# FMC_Memory.net
KiCad netlist of a schematic drawn in Altium Designer
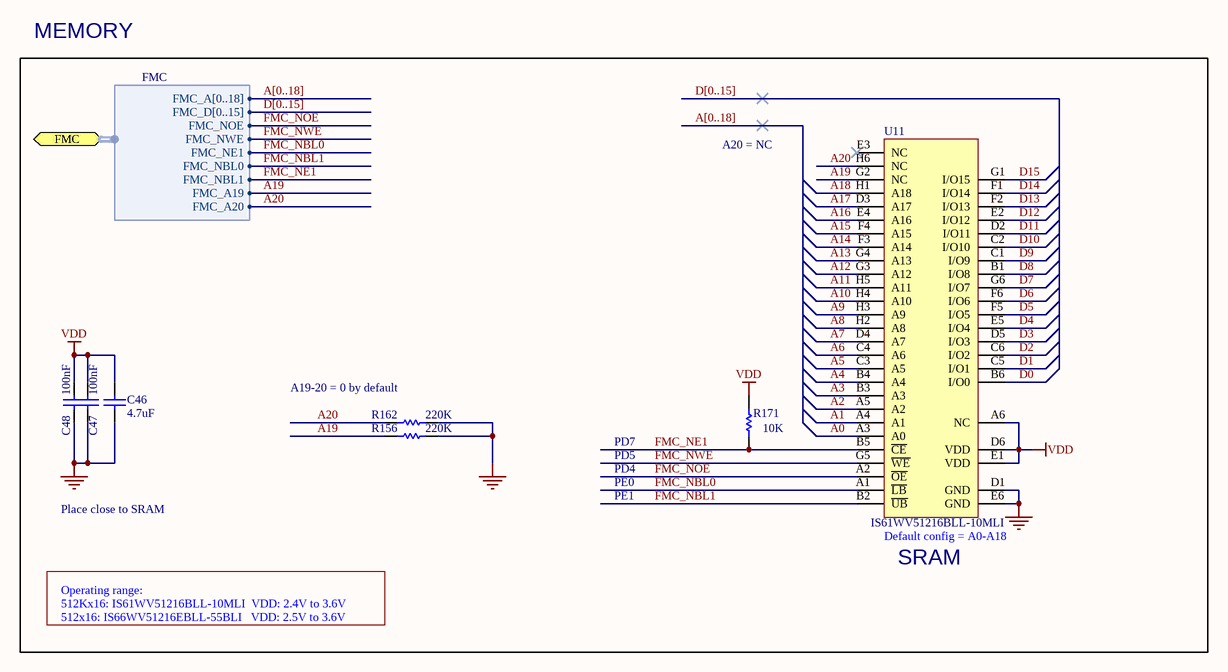
[diagram p0: FMC Memory.SchDoc]

(export (version "E")
  (design (tool "Eeschema 10.0.6"))
  (components
    (comp (ref "C46")
      (value "4.7uF")
      (footprint "C0603")
      (description "Capacitor, MLCC, 4.7uF, 16V, X5R, 10%, 0603, T=0.8mm")
      (fields
        (field (name "INTERNAL_PART_NUMBER") "MCD-00009")
        (field (name "MANUFACTURER_PART_NUMBER") "CC0603KRX5R7BB475")
        (field (name "PROVIDED_BY") "SUBCO")
      )
      (libsource (lib "MCD_PARTS_database") (part "Capacitor"))
    )
    (comp (ref "C47")
      (value "100nF")
      (footprint "C0402")
      (description "Capacitor, MLCC, 100nF, 16V, X7R, 10%, 0402, T=0.5mm")
      (fields
        (field (name "INTERNAL_PART_NUMBER") "MCD-00006")
        (field (name "MANUFACTURER_PART_NUMBER") "CC0402KRX7R7BB104")
        (field (name "PROVIDED_BY") "SUBCO")
      )
      (libsource (lib "MCD_PARTS_database") (part "Capacitor"))
    )
    (comp (ref "C48")
      (value "100nF")
      (footprint "C0402")
      (description "Capacitor, MLCC, 100nF, 16V, X7R, 10%, 0402, T=0.5mm")
      (fields
        (field (name "INTERNAL_PART_NUMBER") "MCD-00006")
        (field (name "MANUFACTURER_PART_NUMBER") "CC0402KRX7R7BB104")
        (field (name "PROVIDED_BY") "SUBCO")
      )
      (libsource (lib "MCD_PARTS_database") (part "Capacitor"))
    )
    (comp (ref "R156")
      (value "220K")
      (footprint "R0402")
      (description "Resistor,220K,0402,1%,1/16W")
      (fields
        (field (name "INTERNAL_PART_NUMBER") "MCD-00164")
        (field (name "MANUFACTURER_PART_NUMBER") "RC0402FR-07220KL")
        (field (name "PROVIDED_BY") "SUBCO")
      )
      (libsource (lib "MCD_PARTS_database") (part "Resistor"))
    )
    (comp (ref "R162")
      (value "220K")
      (footprint "R0402")
      (description "Resistor,220K,0402,1%,1/16W")
      (fields
        (field (name "INTERNAL_PART_NUMBER") "MCD-00164")
        (field (name "MANUFACTURER_PART_NUMBER") "RC0402FR-07220KL")
        (field (name "PROVIDED_BY") "SUBCO")
      )
      (libsource (lib "MCD_PARTS_database") (part "Resistor"))
    )
    (comp (ref "R171")
      (value "10K")
      (footprint "R0402")
      (description "Resistor,10K,0402,1%,1/16W")
      (fields
        (field (name "INTERNAL_PART_NUMBER") "MCD-00053")
        (field (name "MANUFACTURER_PART_NUMBER") "RC0402FR-0710KL")
        (field (name "PROVIDED_BY") "SUBCO")
      )
      (libsource (lib "MCD_PARTS_database") (part "Resistor"))
    )
    (comp (ref "U11")
      (value "IS61WV51216BLL-10MLI")
      (footprint "ICC_MINI-BGA48_9X11_P075")
      (description "SRAM, 8Mb, 10ns, 512Kx16bits, Async, 3.3v")
      (fields
        (field (name "INTERNAL_PART_NUMBER") "MCD-01071")
        (field (name "MANUFACTURER") "ISSI")
        (field (name "PROVIDED_BY") "SUBCO")
      )
      (libsource (lib "MCD_PARTS_database") (part "IS61WV51216BLL-10MLI"))
    )
  )
  (nets
    (net (code "2") (name "/A0") (class "Default")
      (node (ref "U11") (pin "A3") (pinfunction "A0_A3") (pintype "passive"))
    )
    (net (code "3") (name "/A1") (class "Default")
      (node (ref "U11") (pin "A4") (pinfunction "A1_A4") (pintype "passive"))
    )
    (net (code "4") (name "/A2") (class "Default")
      (node (ref "U11") (pin "A5") (pinfunction "A2_A5") (pintype "passive"))
    )
    (net (code "5") (name "/A3") (class "Default")
      (node (ref "U11") (pin "B3") (pinfunction "A3_B3") (pintype "passive"))
    )
    (net (code "6") (name "/A4") (class "Default")
      (node (ref "U11") (pin "B4") (pinfunction "A4_B4") (pintype "passive"))
    )
    (net (code "7") (name "/A5") (class "Default")
      (node (ref "U11") (pin "C3") (pinfunction "A5_C3") (pintype "passive"))
    )
    (net (code "8") (name "/A6") (class "Default")
      (node (ref "U11") (pin "C4") (pinfunction "A6_C4") (pintype "passive"))
    )
    (net (code "9") (name "/A7") (class "Default")
      (node (ref "U11") (pin "D4") (pinfunction "A7_D4") (pintype "passive"))
    )
    (net (code "10") (name "/A8") (class "Default")
      (node (ref "U11") (pin "H2") (pinfunction "A8_H2") (pintype "passive"))
    )
    (net (code "11") (name "/A9") (class "Default")
      (node (ref "U11") (pin "H3") (pinfunction "A9_H3") (pintype "passive"))
    )
    (net (code "12") (name "/A10") (class "Default")
      (node (ref "U11") (pin "H4") (pinfunction "A10_H4") (pintype "passive"))
    )
    (net (code "13") (name "/A11") (class "Default")
      (node (ref "U11") (pin "H5") (pinfunction "A11_H5") (pintype "passive"))
    )
    (net (code "14") (name "/A12") (class "Default")
      (node (ref "U11") (pin "G3") (pinfunction "A12_G3") (pintype "passive"))
    )
    (net (code "15") (name "/A13") (class "Default")
      (node (ref "U11") (pin "G4") (pinfunction "A13_G4") (pintype "passive"))
    )
    (net (code "16") (name "/A14") (class "Default")
      (node (ref "U11") (pin "F3") (pinfunction "A14_F3") (pintype "passive"))
    )
    (net (code "17") (name "/A15") (class "Default")
      (node (ref "U11") (pin "F4") (pinfunction "A15_F4") (pintype "passive"))
    )
    (net (code "18") (name "/A16") (class "Default")
      (node (ref "U11") (pin "E4") (pinfunction "A16_E4") (pintype "passive"))
    )
    (net (code "19") (name "/A17") (class "Default")
      (node (ref "U11") (pin "D3") (pinfunction "A17_D3") (pintype "passive"))
    )
    (net (code "20") (name "/A18") (class "Default")
      (node (ref "U11") (pin "H1") (pinfunction "A18_H1") (pintype "passive"))
    )
    (net (code "21") (name "/A19") (class "Default")
      (node (ref "R156") (pin "2") (pinfunction "2_2") (pintype "passive"))
      (node (ref "U11") (pin "G2") (pinfunction "NC_G2") (pintype "passive"))
    )
    (net (code "22") (name "/A20") (class "Default")
      (node (ref "R162") (pin "2") (pinfunction "2_2") (pintype "passive"))
      (node (ref "U11") (pin "H6") (pinfunction "NC_H6") (pintype "passive"))
    )
    (net (code "24") (name "/D0") (class "Default")
      (node (ref "U11") (pin "B6") (pinfunction "I/O0_B6") (pintype "passive"))
    )
    (net (code "25") (name "/D1") (class "Default")
      (node (ref "U11") (pin "C5") (pinfunction "I/O1_C5") (pintype "passive"))
    )
    (net (code "26") (name "/D2") (class "Default")
      (node (ref "U11") (pin "C6") (pinfunction "I/O2_C6") (pintype "passive"))
    )
    (net (code "27") (name "/D3") (class "Default")
      (node (ref "U11") (pin "D5") (pinfunction "I/O3_D5") (pintype "passive"))
    )
    (net (code "28") (name "/D4") (class "Default")
      (node (ref "U11") (pin "E5") (pinfunction "I/O4_E5") (pintype "passive"))
    )
    (net (code "29") (name "/D5") (class "Default")
      (node (ref "U11") (pin "F5") (pinfunction "I/O5_F5") (pintype "passive"))
    )
    (net (code "30") (name "/D6") (class "Default")
      (node (ref "U11") (pin "F6") (pinfunction "I/O6_F6") (pintype "passive"))
    )
    (net (code "31") (name "/D7") (class "Default")
      (node (ref "U11") (pin "G6") (pinfunction "I/O7_G6") (pintype "passive"))
    )
    (net (code "32") (name "/D8") (class "Default")
      (node (ref "U11") (pin "B1") (pinfunction "I/O8_B1") (pintype "passive"))
    )
    (net (code "33") (name "/D9") (class "Default")
      (node (ref "U11") (pin "C1") (pinfunction "I/O9_C1") (pintype "passive"))
    )
    (net (code "34") (name "/D10") (class "Default")
      (node (ref "U11") (pin "C2") (pinfunction "I/O10_C2") (pintype "passive"))
    )
    (net (code "35") (name "/D11") (class "Default")
      (node (ref "U11") (pin "D2") (pinfunction "I/O11_D2") (pintype "passive"))
    )
    (net (code "36") (name "/D12") (class "Default")
      (node (ref "U11") (pin "E2") (pinfunction "I/O12_E2") (pintype "passive"))
    )
    (net (code "37") (name "/D13") (class "Default")
      (node (ref "U11") (pin "F2") (pinfunction "I/O13_F2") (pintype "passive"))
    )
    (net (code "38") (name "/D14") (class "Default")
      (node (ref "U11") (pin "F1") (pinfunction "I/O14_F1") (pintype "passive"))
    )
    (net (code "39") (name "/D15") (class "Default")
      (node (ref "U11") (pin "G1") (pinfunction "I/O15_G1") (pintype "passive"))
    )
    (net (code "41") (name "/FMC_NBL0") (class "Default")
      (node (ref "U11") (pin "A1") (pinfunction "~{LB}_A1") (pintype "passive"))
    )
    (net (code "42") (name "/FMC_NBL1") (class "Default")
      (node (ref "U11") (pin "B2") (pinfunction "~{UB}_B2") (pintype "passive"))
    )
    (net (code "43") (name "/FMC_NE1") (class "Default")
      (node (ref "R171") (pin "1") (pinfunction "1_1") (pintype "passive"))
      (node (ref "U11") (pin "B5") (pinfunction "~{CE}_B5") (pintype "passive"))
    )
    (net (code "44") (name "/FMC_NOE") (class "Default")
      (node (ref "U11") (pin "A2") (pinfunction "~{OE}_A2") (pintype "passive"))
    )
    (net (code "45") (name "/FMC_NWE") (class "Default")
      (node (ref "U11") (pin "G5") (pinfunction "~{WE}_G5") (pintype "passive"))
    )
    (net (code "48") (name "GND") (class "Default")
      (node (ref "C46") (pin "1") (pinfunction "1_1") (pintype "passive"))
      (node (ref "C47") (pin "2") (pinfunction "2_2") (pintype "passive"))
      (node (ref "C48") (pin "2") (pinfunction "2_2") (pintype "passive"))
      (node (ref "R156") (pin "1") (pinfunction "1_1") (pintype "passive"))
      (node (ref "R162") (pin "1") (pinfunction "1_1") (pintype "passive"))
      (node (ref "U11") (pin "D1") (pinfunction "GND_D1") (pintype "passive"))
      (node (ref "U11") (pin "E6") (pinfunction "GND_E6") (pintype "passive"))
    )
    (net (code "49") (name "VDD") (class "Default")
      (node (ref "C46") (pin "2") (pinfunction "2_2") (pintype "passive"))
      (node (ref "C47") (pin "1") (pinfunction "1_1") (pintype "passive"))
      (node (ref "C48") (pin "1") (pinfunction "1_1") (pintype "passive"))
      (node (ref "R171") (pin "2") (pinfunction "2_2") (pintype "passive"))
      (node (ref "U11") (pin "A6") (pinfunction "NC_A6") (pintype "passive"))
      (node (ref "U11") (pin "D6") (pinfunction "VDD_D6") (pintype "passive"))
      (node (ref "U11") (pin "E1") (pinfunction "VDD_E1") (pintype "passive"))
    )
    (net (code "50") (name "unconnected-(U11-NC-PadE3)") (class "Default")
      (node (ref "U11") (pin "E3") (pinfunction "NC_E3") (pintype "passive+no_connect"))
    )
  )
)
